# f1042-2.net
KiCad netlist of a schematic drawn in EAGLE
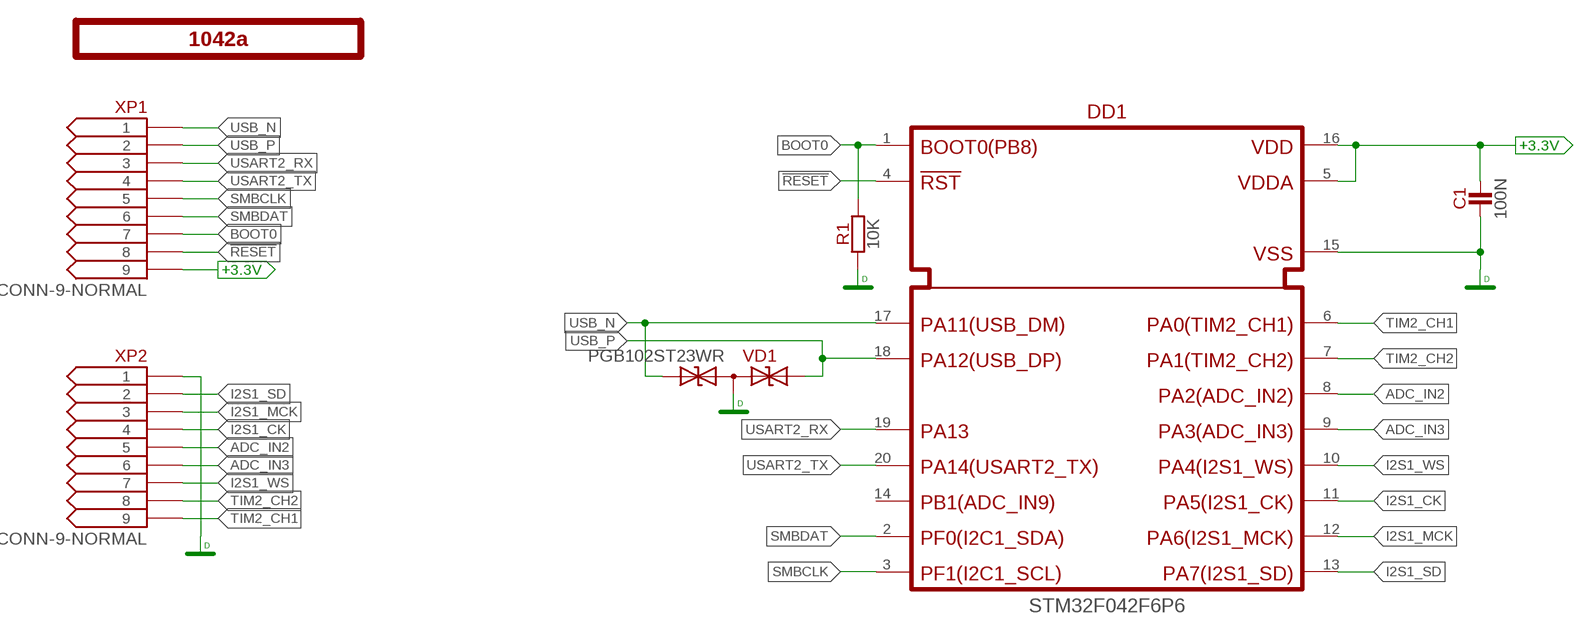
[diagram p0: schematic, sheet 1]

(export (version "E")
  (design (tool "Eeschema 10.0.6"))
  (components
    (comp (ref "C1")
      (value "100N")
      (footprint "eagle-import:C-0805")
      (libsource (lib "eagle-import") (part "?100N"))
    )
    (comp (ref "DD1")
      (value "STM32F042F6P6")
      (footprint "eagle-import:TSSOP20")
      (libsource (lib "eagle-import") (part "STM32F042F6P6"))
    )
    (comp (ref "PCB1")
      (value "1042a")
      (footprint "eagle-import:F-LOGO")
      (libsource (lib "eagle-import") (part "GENERIC-LOGO"))
    )
    (comp (ref "R1")
      (value "10K")
      (footprint "eagle-import:R-0805")
      (libsource (lib "eagle-import") (part "?10K"))
    )
    (comp (ref "VD1")
      (value "PGB102ST23WR")
      (footprint "eagle-import:SOT23")
      (libsource (lib "eagle-import") (part "PGB102ST23WR"))
    )
    (comp (ref "XP1")
      (value "CONN-9-NORMAL")
      (footprint "eagle-import:MA03-9")
      (libsource (lib "eagle-import") (part "CONN-9-?NORMAL"))
    )
    (comp (ref "XP2")
      (value "CONN-9-NORMAL")
      (footprint "eagle-import:MA03-9")
      (libsource (lib "eagle-import") (part "CONN-9-?NORMAL"))
    )
  )
  (nets
    (net (code "1") (name "+3.3V") (class "Default")
      (node (ref "C1") (pin "2") (pinfunction "2_2") (pintype "passive"))
      (node (ref "DD1") (pin "16") (pinfunction "VDD_16") (pintype "input"))
      (node (ref "DD1") (pin "5") (pinfunction "VDDA_5") (pintype "input"))
      (node (ref "XP1") (pin "9") (pinfunction "9_9") (pintype "passive"))
    )
    (net (code "2") (name "/~{RESET}") (class "Default")
      (node (ref "DD1") (pin "4") (pinfunction "~{RST}_4") (pintype "input"))
      (node (ref "XP1") (pin "8") (pinfunction "8_8") (pintype "passive"))
    )
    (net (code "3") (name "ADC_IN2") (class "Default")
      (node (ref "DD1") (pin "8") (pinfunction "PA2_8") (pintype "input"))
      (node (ref "XP2") (pin "5") (pinfunction "5_5") (pintype "passive"))
    )
    (net (code "4") (name "ADC_IN3") (class "Default")
      (node (ref "DD1") (pin "9") (pinfunction "PA3_9") (pintype "input"))
      (node (ref "XP2") (pin "6") (pinfunction "6_6") (pintype "passive"))
    )
    (net (code "5") (name "BOOT0") (class "Default")
      (node (ref "DD1") (pin "1") (pinfunction "BOOT0_1") (pintype "input"))
      (node (ref "R1") (pin "2") (pinfunction "2_2") (pintype "passive"))
      (node (ref "XP1") (pin "7") (pinfunction "7_7") (pintype "passive"))
    )
    (net (code "6") (name "DGND") (class "Default")
      (node (ref "C1") (pin "1") (pinfunction "1_1") (pintype "passive"))
      (node (ref "DD1") (pin "15") (pinfunction "VSS_15") (pintype "input"))
      (node (ref "R1") (pin "1") (pinfunction "1_1") (pintype "passive"))
      (node (ref "VD1") (pin "3") (pinfunction "C_3") (pintype "passive"))
      (node (ref "XP2") (pin "1") (pinfunction "1_1") (pintype "passive"))
    )
    (net (code "7") (name "I2S1_CK") (class "Default")
      (node (ref "DD1") (pin "11") (pinfunction "PA5_11") (pintype "input"))
      (node (ref "XP2") (pin "4") (pinfunction "4_4") (pintype "passive"))
    )
    (net (code "8") (name "I2S1_MCK") (class "Default")
      (node (ref "DD1") (pin "12") (pinfunction "PA6_12") (pintype "input"))
      (node (ref "XP2") (pin "3") (pinfunction "3_3") (pintype "passive"))
    )
    (net (code "9") (name "I2S1_SD") (class "Default")
      (node (ref "DD1") (pin "13") (pinfunction "PA7_13") (pintype "input"))
      (node (ref "XP2") (pin "2") (pinfunction "2_2") (pintype "passive"))
    )
    (net (code "10") (name "I2S1_WS") (class "Default")
      (node (ref "DD1") (pin "10") (pinfunction "PA4_10") (pintype "input"))
      (node (ref "XP2") (pin "7") (pinfunction "7_7") (pintype "passive"))
    )
    (net (code "11") (name "SMBCLK") (class "Default")
      (node (ref "DD1") (pin "3") (pinfunction "PF1_3") (pintype "input"))
      (node (ref "XP1") (pin "5") (pinfunction "5_5") (pintype "passive"))
    )
    (net (code "12") (name "SMBDAT") (class "Default")
      (node (ref "DD1") (pin "2") (pinfunction "PF0_2") (pintype "input"))
      (node (ref "XP1") (pin "6") (pinfunction "6_6") (pintype "passive"))
    )
    (net (code "13") (name "TIM2_CH1") (class "Default")
      (node (ref "DD1") (pin "6") (pinfunction "PA0_6") (pintype "input"))
      (node (ref "XP2") (pin "9") (pinfunction "9_9") (pintype "passive"))
    )
    (net (code "14") (name "TIM2_CH2") (class "Default")
      (node (ref "DD1") (pin "7") (pinfunction "PA1_7") (pintype "input"))
      (node (ref "XP2") (pin "8") (pinfunction "8_8") (pintype "passive"))
    )
    (net (code "15") (name "USART2_RX") (class "Default")
      (node (ref "DD1") (pin "19") (pinfunction "PA13_19") (pintype "input"))
      (node (ref "XP1") (pin "3") (pinfunction "3_3") (pintype "passive"))
    )
    (net (code "16") (name "USART2_TX") (class "Default")
      (node (ref "DD1") (pin "20") (pinfunction "PA14_20") (pintype "input"))
      (node (ref "XP1") (pin "4") (pinfunction "4_4") (pintype "passive"))
    )
    (net (code "17") (name "USB_N") (class "Default")
      (node (ref "DD1") (pin "17") (pinfunction "PA11_17") (pintype "input"))
      (node (ref "VD1") (pin "2") (pinfunction "A1_2") (pintype "passive"))
      (node (ref "XP1") (pin "1") (pinfunction "1_1") (pintype "passive"))
    )
    (net (code "18") (name "USB_P") (class "Default")
      (node (ref "DD1") (pin "18") (pinfunction "PA12_18") (pintype "input"))
      (node (ref "VD1") (pin "1") (pinfunction "A_1") (pintype "passive"))
      (node (ref "XP1") (pin "2") (pinfunction "2_2") (pintype "passive"))
    )
    (net (code "19") (name "unconnected-(DD1-PB1-Pad14)") (class "Default")
      (node (ref "DD1") (pin "14") (pinfunction "PB1_14") (pintype "input"))
    )
  )
)
